# 1U_attenuvert.net
KiCad netlist of a schematic drawn in EAGLE
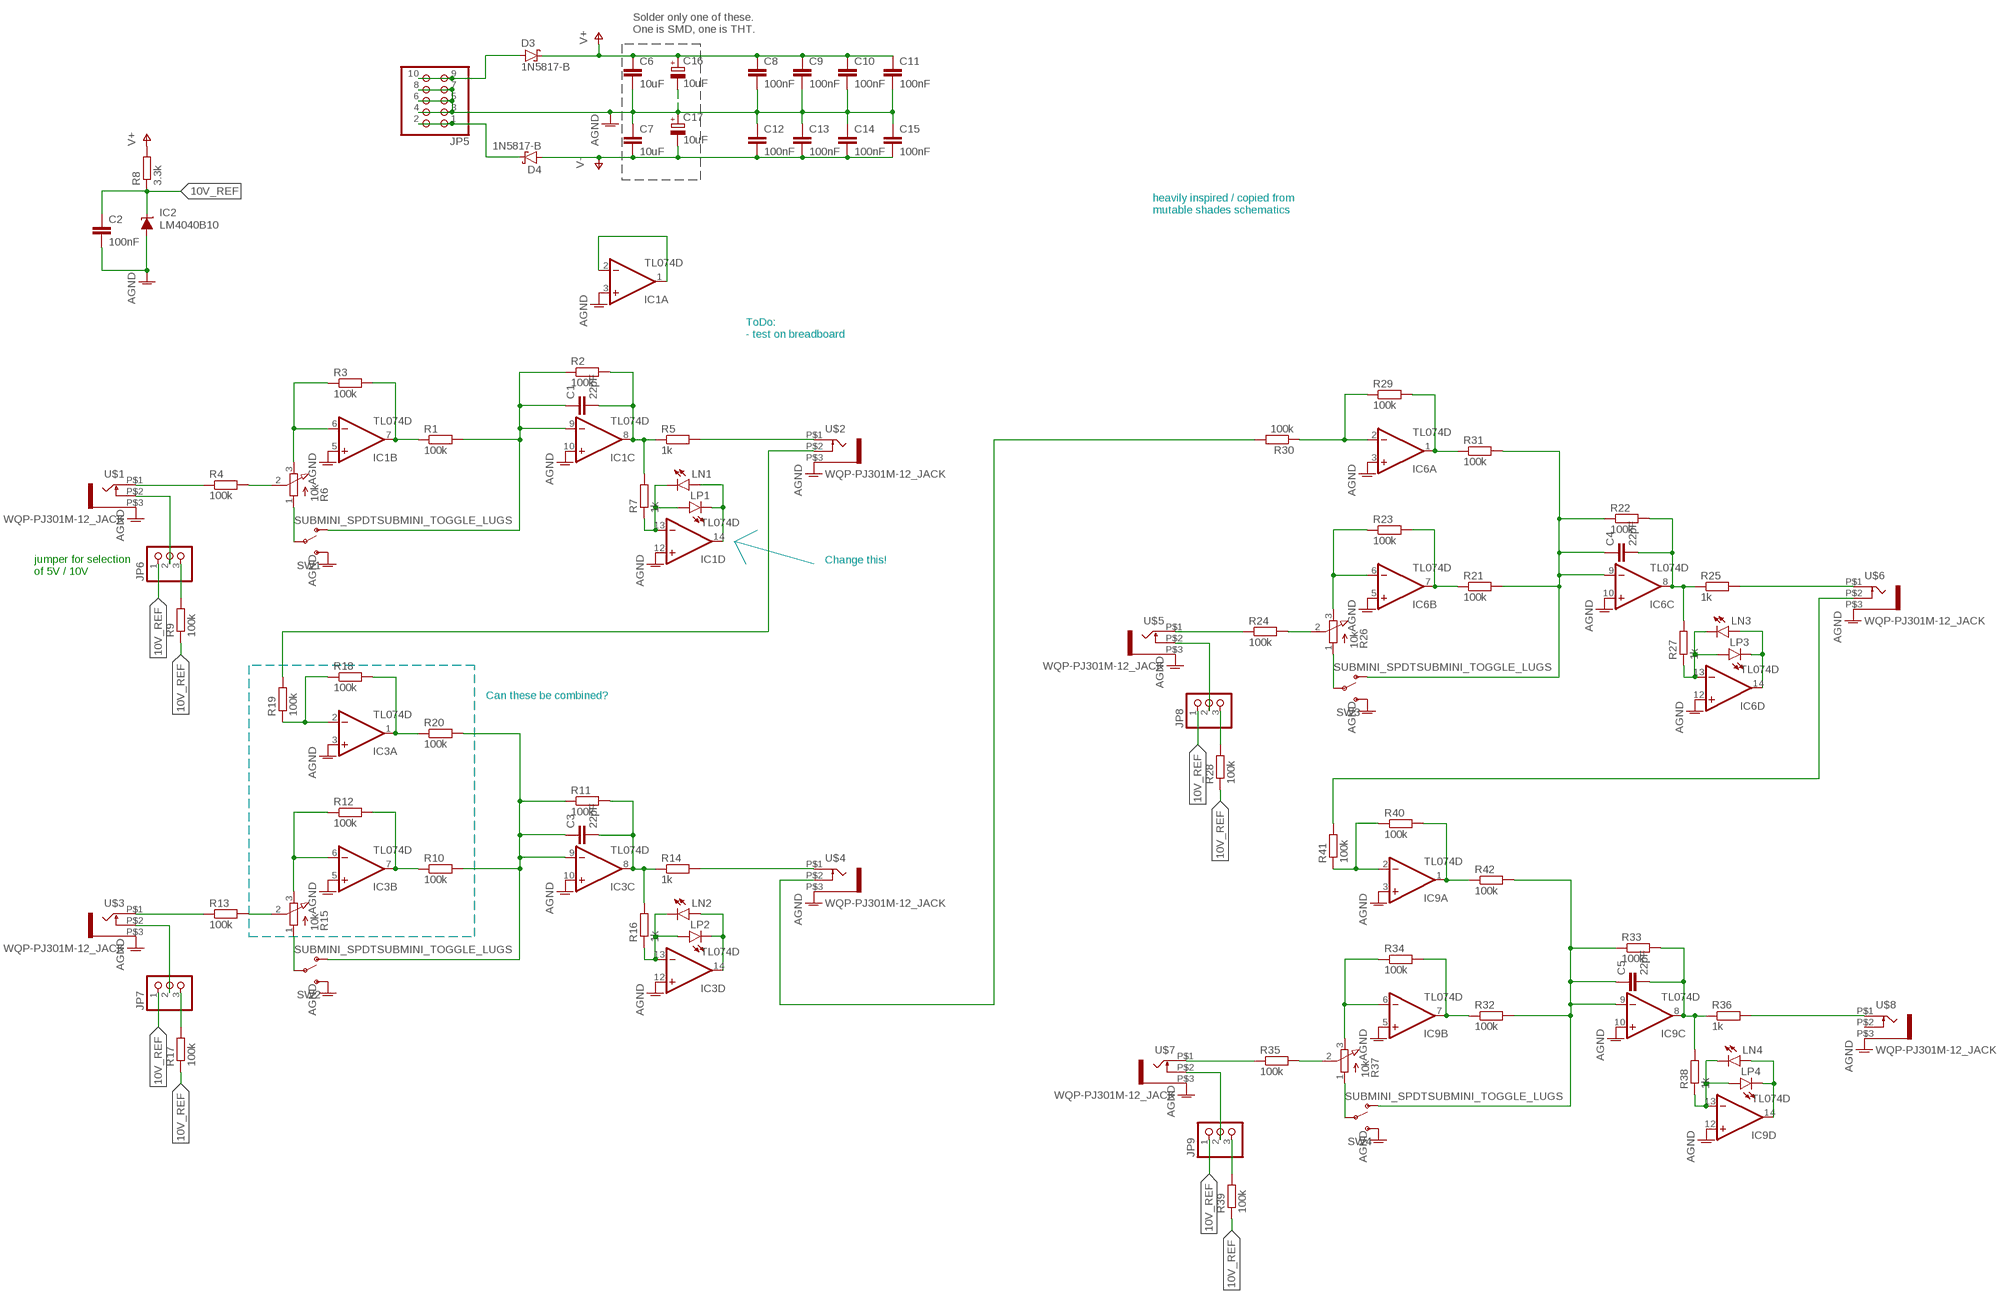
[diagram p0: schematic, sheet 1]

(export (version "E")
  (design (tool "Eeschema 10.0.6"))
  (components
    (comp (ref "C1")
      (value "22pF")
      (footprint "eagle-import:C0603")
      (libsource (lib "eagle-import") (part "C-EUC0603"))
    )
    (comp (ref "C2")
      (value "100nF")
      (footprint "eagle-import:C0603")
      (libsource (lib "eagle-import") (part "C-EUC0603"))
    )
    (comp (ref "C3")
      (value "22pF")
      (footprint "eagle-import:C0603")
      (libsource (lib "eagle-import") (part "C-EUC0603"))
    )
    (comp (ref "C4")
      (value "22pF")
      (footprint "eagle-import:C0603")
      (libsource (lib "eagle-import") (part "C-EUC0603"))
    )
    (comp (ref "C5")
      (value "22pF")
      (footprint "eagle-import:C0603")
      (libsource (lib "eagle-import") (part "C-EUC0603"))
    )
    (comp (ref "C6")
      (value "10uF")
      (footprint "eagle-import:C0805")
      (libsource (lib "eagle-import") (part "C-EUC0805"))
    )
    (comp (ref "C7")
      (value "10uF")
      (footprint "eagle-import:C0805")
      (libsource (lib "eagle-import") (part "C-EUC0805"))
    )
    (comp (ref "C8")
      (value "100nF")
      (footprint "eagle-import:C0603")
      (libsource (lib "eagle-import") (part "C-EUC0603"))
    )
    (comp (ref "C9")
      (value "100nF")
      (footprint "eagle-import:C0603")
      (libsource (lib "eagle-import") (part "C-EUC0603"))
    )
    (comp (ref "C10")
      (value "100nF")
      (footprint "eagle-import:C0603")
      (libsource (lib "eagle-import") (part "C-EUC0603"))
    )
    (comp (ref "C11")
      (value "100nF")
      (footprint "eagle-import:C0603")
      (libsource (lib "eagle-import") (part "C-EUC0603"))
    )
    (comp (ref "C12")
      (value "100nF")
      (footprint "eagle-import:C0603")
      (libsource (lib "eagle-import") (part "C-EUC0603"))
    )
    (comp (ref "C13")
      (value "100nF")
      (footprint "eagle-import:C0603")
      (libsource (lib "eagle-import") (part "C-EUC0603"))
    )
    (comp (ref "C14")
      (value "100nF")
      (footprint "eagle-import:C0603")
      (libsource (lib "eagle-import") (part "C-EUC0603"))
    )
    (comp (ref "C15")
      (value "100nF")
      (footprint "eagle-import:C0603")
      (libsource (lib "eagle-import") (part "C-EUC0603"))
    )
    (comp (ref "C16")
      (value "10uF")
      (footprint "eagle-import:E2,5-6")
      (libsource (lib "eagle-import") (part "CPOL-EUE2.5-6"))
    )
    (comp (ref "C17")
      (value "10uF")
      (footprint "eagle-import:E2,5-6")
      (libsource (lib "eagle-import") (part "CPOL-EUE2.5-6"))
    )
    (comp (ref "D3")
      (value "1N5817-B")
      (footprint "eagle-import:DO41-7.6")
      (libsource (lib "eagle-import") (part "1N5817-B"))
    )
    (comp (ref "D4")
      (value "1N5817-B")
      (footprint "eagle-import:DO41-7.6")
      (libsource (lib "eagle-import") (part "1N5817-B"))
    )
    (comp (ref "IC1")
      (value "TL074D")
      (footprint "eagle-import:SO14")
      (libsource (lib "eagle-import") (part "TL074D"))
    )
    (comp (ref "IC2")
      (value "LM4040B10")
      (footprint "eagle-import:DBZ_R-PDSO-G3")
      (fields (field (name "MPN") "LM4041A12IDBZR"))
      (libsource (lib "eagle-import") (part "LM4041DBZA12"))
    )
    (comp (ref "IC3")
      (value "TL074D")
      (footprint "eagle-import:SO14")
      (libsource (lib "eagle-import") (part "TL074D"))
    )
    (comp (ref "IC6")
      (value "TL074D")
      (footprint "eagle-import:SO14")
      (libsource (lib "eagle-import") (part "TL074D"))
    )
    (comp (ref "IC9")
      (value "TL074D")
      (footprint "eagle-import:SO14")
      (libsource (lib "eagle-import") (part "TL074D"))
    )
    (comp (ref "JP5")
      (value "PINHD-2X5")
      (footprint "eagle-import:2X05")
      (libsource (lib "eagle-import") (part "PINHD-2X5"))
    )
    (comp (ref "JP6")
      (value "PINHD-1X3")
      (footprint "eagle-import:1X03")
      (libsource (lib "eagle-import") (part "PINHD-1X3"))
    )
    (comp (ref "JP7")
      (value "PINHD-1X3")
      (footprint "eagle-import:1X03")
      (libsource (lib "eagle-import") (part "PINHD-1X3"))
    )
    (comp (ref "JP8")
      (value "PINHD-1X3")
      (footprint "eagle-import:1X03")
      (libsource (lib "eagle-import") (part "PINHD-1X3"))
    )
    (comp (ref "JP9")
      (value "PINHD-1X3")
      (footprint "eagle-import:1X03")
      (libsource (lib "eagle-import") (part "PINHD-1X3"))
    )
    (comp (ref "LN1")
      (value "LED3MM")
      (footprint "eagle-import:LED3MM")
      (libsource (lib "eagle-import") (part "LED3MM"))
    )
    (comp (ref "LN2")
      (value "LED3MM")
      (footprint "eagle-import:LED3MM")
      (libsource (lib "eagle-import") (part "LED3MM"))
    )
    (comp (ref "LN3")
      (value "LED3MM")
      (footprint "eagle-import:LED3MM")
      (libsource (lib "eagle-import") (part "LED3MM"))
    )
    (comp (ref "LN4")
      (value "LED3MM")
      (footprint "eagle-import:LED3MM")
      (libsource (lib "eagle-import") (part "LED3MM"))
    )
    (comp (ref "LP1")
      (value "LED3MM")
      (footprint "eagle-import:LED3MM")
      (libsource (lib "eagle-import") (part "LED3MM"))
    )
    (comp (ref "LP2")
      (value "LED3MM")
      (footprint "eagle-import:LED3MM")
      (libsource (lib "eagle-import") (part "LED3MM"))
    )
    (comp (ref "LP3")
      (value "LED3MM")
      (footprint "eagle-import:LED3MM")
      (libsource (lib "eagle-import") (part "LED3MM"))
    )
    (comp (ref "LP4")
      (value "LED3MM")
      (footprint "eagle-import:LED3MM")
      (libsource (lib "eagle-import") (part "LED3MM"))
    )
    (comp (ref "R1")
      (value "100k")
      (footprint "eagle-import:R0603")
      (libsource (lib "eagle-import") (part "R-EU_R0603"))
    )
    (comp (ref "R2")
      (value "100k")
      (footprint "eagle-import:R0603")
      (libsource (lib "eagle-import") (part "R-EU_R0603"))
    )
    (comp (ref "R3")
      (value "100k")
      (footprint "eagle-import:R0603")
      (libsource (lib "eagle-import") (part "R-EU_R0603"))
    )
    (comp (ref "R4")
      (value "100k")
      (footprint "eagle-import:R0603")
      (libsource (lib "eagle-import") (part "R-EU_R0603"))
    )
    (comp (ref "R5")
      (value "1k")
      (footprint "eagle-import:R0603")
      (libsource (lib "eagle-import") (part "R-EU_R0603"))
    )
    (comp (ref "R6")
      (value "10k")
      (footprint "eagle-import:EVUFXL")
      (libsource (lib "eagle-import") (part "EVULF2"))
    )
    (comp (ref "R7")
      (value "1k")
      (footprint "eagle-import:R0603")
      (libsource (lib "eagle-import") (part "R-EU_R0603"))
    )
    (comp (ref "R8")
      (value "3.3k")
      (footprint "eagle-import:R0603")
      (libsource (lib "eagle-import") (part "R-EU_R0603"))
    )
    (comp (ref "R9")
      (value "100k")
      (footprint "eagle-import:R0603")
      (libsource (lib "eagle-import") (part "R-EU_R0603"))
    )
    (comp (ref "R10")
      (value "100k")
      (footprint "eagle-import:R0603")
      (libsource (lib "eagle-import") (part "R-EU_R0603"))
    )
    (comp (ref "R11")
      (value "100k")
      (footprint "eagle-import:R0603")
      (libsource (lib "eagle-import") (part "R-EU_R0603"))
    )
    (comp (ref "R12")
      (value "100k")
      (footprint "eagle-import:R0603")
      (libsource (lib "eagle-import") (part "R-EU_R0603"))
    )
    (comp (ref "R13")
      (value "100k")
      (footprint "eagle-import:R0603")
      (libsource (lib "eagle-import") (part "R-EU_R0603"))
    )
    (comp (ref "R14")
      (value "1k")
      (footprint "eagle-import:R0603")
      (libsource (lib "eagle-import") (part "R-EU_R0603"))
    )
    (comp (ref "R15")
      (value "10k")
      (footprint "eagle-import:EVUFXL")
      (libsource (lib "eagle-import") (part "EVULF2"))
    )
    (comp (ref "R16")
      (value "1k")
      (footprint "eagle-import:R0603")
      (libsource (lib "eagle-import") (part "R-EU_R0603"))
    )
    (comp (ref "R17")
      (value "100k")
      (footprint "eagle-import:R0603")
      (libsource (lib "eagle-import") (part "R-EU_R0603"))
    )
    (comp (ref "R18")
      (value "100k")
      (footprint "eagle-import:R0603")
      (libsource (lib "eagle-import") (part "R-EU_R0603"))
    )
    (comp (ref "R19")
      (value "100k")
      (footprint "eagle-import:R0603")
      (libsource (lib "eagle-import") (part "R-EU_R0603"))
    )
    (comp (ref "R20")
      (value "100k")
      (footprint "eagle-import:R0603")
      (libsource (lib "eagle-import") (part "R-EU_R0603"))
    )
    (comp (ref "R21")
      (value "100k")
      (footprint "eagle-import:R0603")
      (libsource (lib "eagle-import") (part "R-EU_R0603"))
    )
    (comp (ref "R22")
      (value "100k")
      (footprint "eagle-import:R0603")
      (libsource (lib "eagle-import") (part "R-EU_R0603"))
    )
    (comp (ref "R23")
      (value "100k")
      (footprint "eagle-import:R0603")
      (libsource (lib "eagle-import") (part "R-EU_R0603"))
    )
    (comp (ref "R24")
      (value "100k")
      (footprint "eagle-import:R0603")
      (libsource (lib "eagle-import") (part "R-EU_R0603"))
    )
    (comp (ref "R25")
      (value "1k")
      (footprint "eagle-import:R0603")
      (libsource (lib "eagle-import") (part "R-EU_R0603"))
    )
    (comp (ref "R26")
      (value "10k")
      (footprint "eagle-import:EVUFXL")
      (libsource (lib "eagle-import") (part "EVULF2"))
    )
    (comp (ref "R27")
      (value "1k")
      (footprint "eagle-import:R0603")
      (libsource (lib "eagle-import") (part "R-EU_R0603"))
    )
    (comp (ref "R28")
      (value "100k")
      (footprint "eagle-import:R0603")
      (libsource (lib "eagle-import") (part "R-EU_R0603"))
    )
    (comp (ref "R29")
      (value "100k")
      (footprint "eagle-import:R0603")
      (libsource (lib "eagle-import") (part "R-EU_R0603"))
    )
    (comp (ref "R30")
      (value "100k")
      (footprint "eagle-import:R0603")
      (libsource (lib "eagle-import") (part "R-EU_R0603"))
    )
    (comp (ref "R31")
      (value "100k")
      (footprint "eagle-import:R0603")
      (libsource (lib "eagle-import") (part "R-EU_R0603"))
    )
    (comp (ref "R32")
      (value "100k")
      (footprint "eagle-import:R0603")
      (libsource (lib "eagle-import") (part "R-EU_R0603"))
    )
    (comp (ref "R33")
      (value "100k")
      (footprint "eagle-import:R0603")
      (libsource (lib "eagle-import") (part "R-EU_R0603"))
    )
    (comp (ref "R34")
      (value "100k")
      (footprint "eagle-import:R0603")
      (libsource (lib "eagle-import") (part "R-EU_R0603"))
    )
    (comp (ref "R35")
      (value "100k")
      (footprint "eagle-import:R0603")
      (libsource (lib "eagle-import") (part "R-EU_R0603"))
    )
    (comp (ref "R36")
      (value "1k")
      (footprint "eagle-import:R0603")
      (libsource (lib "eagle-import") (part "R-EU_R0603"))
    )
    (comp (ref "R37")
      (value "10k")
      (footprint "eagle-import:EVUFXL")
      (libsource (lib "eagle-import") (part "EVULF2"))
    )
    (comp (ref "R38")
      (value "1k")
      (footprint "eagle-import:R0603")
      (libsource (lib "eagle-import") (part "R-EU_R0603"))
    )
    (comp (ref "R39")
      (value "100k")
      (footprint "eagle-import:R0603")
      (libsource (lib "eagle-import") (part "R-EU_R0603"))
    )
    (comp (ref "R40")
      (value "100k")
      (footprint "eagle-import:R0603")
      (libsource (lib "eagle-import") (part "R-EU_R0603"))
    )
    (comp (ref "R41")
      (value "100k")
      (footprint "eagle-import:R0603")
      (libsource (lib "eagle-import") (part "R-EU_R0603"))
    )
    (comp (ref "R42")
      (value "100k")
      (footprint "eagle-import:R0603")
      (libsource (lib "eagle-import") (part "R-EU_R0603"))
    )
    (comp (ref "SW1")
      (value "SUBMINI_SPDTSUBMINI_TOGGLE_LUGS")
      (footprint "eagle-import:SUBMINI_TOGGLE_LUGS")
      (libsource (lib "eagle-import") (part "SUBMINI_SPDTSUBMINI_TOGGLE_LUGS"))
    )
    (comp (ref "SW2")
      (value "SUBMINI_SPDTSUBMINI_TOGGLE_LUGS")
      (footprint "eagle-import:SUBMINI_TOGGLE_LUGS")
      (libsource (lib "eagle-import") (part "SUBMINI_SPDTSUBMINI_TOGGLE_LUGS"))
    )
    (comp (ref "SW3")
      (value "SUBMINI_SPDTSUBMINI_TOGGLE_LUGS")
      (footprint "eagle-import:SUBMINI_TOGGLE_LUGS")
      (libsource (lib "eagle-import") (part "SUBMINI_SPDTSUBMINI_TOGGLE_LUGS"))
    )
    (comp (ref "SW4")
      (value "SUBMINI_SPDTSUBMINI_TOGGLE_LUGS")
      (footprint "eagle-import:SUBMINI_TOGGLE_LUGS")
      (libsource (lib "eagle-import") (part "SUBMINI_SPDTSUBMINI_TOGGLE_LUGS"))
    )
    (comp (ref "U$1")
      (value "WQP-PJ301M-12_JACK")
      (footprint "eagle-import:WQP-PJ301M-12_JACK")
      (libsource (lib "eagle-import") (part "WQP-PJ301M-12_JACK"))
    )
    (comp (ref "U$2")
      (value "WQP-PJ301M-12_JACK")
      (footprint "eagle-import:WQP-PJ301M-12_JACK")
      (libsource (lib "eagle-import") (part "WQP-PJ301M-12_JACK"))
    )
    (comp (ref "U$3")
      (value "WQP-PJ301M-12_JACK")
      (footprint "eagle-import:WQP-PJ301M-12_JACK")
      (libsource (lib "eagle-import") (part "WQP-PJ301M-12_JACK"))
    )
    (comp (ref "U$4")
      (value "WQP-PJ301M-12_JACK")
      (footprint "eagle-import:WQP-PJ301M-12_JACK")
      (libsource (lib "eagle-import") (part "WQP-PJ301M-12_JACK"))
    )
    (comp (ref "U$5")
      (value "WQP-PJ301M-12_JACK")
      (footprint "eagle-import:WQP-PJ301M-12_JACK")
      (libsource (lib "eagle-import") (part "WQP-PJ301M-12_JACK"))
    )
    (comp (ref "U$6")
      (value "WQP-PJ301M-12_JACK")
      (footprint "eagle-import:WQP-PJ301M-12_JACK")
      (libsource (lib "eagle-import") (part "WQP-PJ301M-12_JACK"))
    )
    (comp (ref "U$7")
      (value "WQP-PJ301M-12_JACK")
      (footprint "eagle-import:WQP-PJ301M-12_JACK")
      (libsource (lib "eagle-import") (part "WQP-PJ301M-12_JACK"))
    )
    (comp (ref "U$8")
      (value "WQP-PJ301M-12_JACK")
      (footprint "eagle-import:WQP-PJ301M-12_JACK")
      (libsource (lib "eagle-import") (part "WQP-PJ301M-12_JACK"))
    )
  )
  (nets
    (net (code "1") (name "10V_REF") (class "Default")
      (node (ref "C2") (pin "1") (pinfunction "1_1") (pintype "passive"))
      (node (ref "IC2") (pin "1") (pinfunction "C_1") (pintype "passive"))
      (node (ref "JP6") (pin "1") (pinfunction "1_1") (pintype "passive"))
      (node (ref "JP7") (pin "1") (pinfunction "1_1") (pintype "passive"))
      (node (ref "JP8") (pin "1") (pinfunction "1_1") (pintype "passive"))
      (node (ref "JP9") (pin "1") (pinfunction "1_1") (pintype "passive"))
      (node (ref "R17") (pin "1") (pinfunction "1_1") (pintype "passive"))
      (node (ref "R28") (pin "1") (pinfunction "1_1") (pintype "passive"))
      (node (ref "R39") (pin "1") (pinfunction "1_1") (pintype "passive"))
      (node (ref "R8") (pin "1") (pinfunction "1_1") (pintype "passive"))
      (node (ref "R9") (pin "1") (pinfunction "1_1") (pintype "passive"))
    )
    (net (code "2") (name "AGND") (class "Default")
      (node (ref "C10") (pin "2") (pinfunction "2_2") (pintype "passive"))
      (node (ref "C11") (pin "2") (pinfunction "2_2") (pintype "passive"))
      (node (ref "C12") (pin "1") (pinfunction "1_1") (pintype "passive"))
      (node (ref "C13") (pin "1") (pinfunction "1_1") (pintype "passive"))
      (node (ref "C14") (pin "1") (pinfunction "1_1") (pintype "passive"))
      (node (ref "C15") (pin "1") (pinfunction "1_1") (pintype "passive"))
      (node (ref "C16") (pin "-") (pinfunction "-_-") (pintype "passive"))
      (node (ref "C17") (pin "+") (pinfunction "+_+") (pintype "passive"))
      (node (ref "C2") (pin "2") (pinfunction "2_2") (pintype "passive"))
      (node (ref "C6") (pin "2") (pinfunction "2_2") (pintype "passive"))
      (node (ref "C7") (pin "1") (pinfunction "1_1") (pintype "passive"))
      (node (ref "C8") (pin "2") (pinfunction "2_2") (pintype "passive"))
      (node (ref "C9") (pin "2") (pinfunction "2_2") (pintype "passive"))
      (node (ref "IC1") (pin "10") (pinfunction "+IN_10") (pintype "input"))
      (node (ref "IC1") (pin "12") (pinfunction "+IN_12") (pintype "input"))
      (node (ref "IC1") (pin "3") (pinfunction "+IN_3") (pintype "input"))
      (node (ref "IC1") (pin "5") (pinfunction "+IN_5") (pintype "input"))
      (node (ref "IC2") (pin "2") (pinfunction "A_2") (pintype "passive"))
      (node (ref "IC3") (pin "10") (pinfunction "+IN_10") (pintype "input"))
      (node (ref "IC3") (pin "12") (pinfunction "+IN_12") (pintype "input"))
      (node (ref "IC3") (pin "3") (pinfunction "+IN_3") (pintype "input"))
      (node (ref "IC3") (pin "5") (pinfunction "+IN_5") (pintype "input"))
      (node (ref "IC6") (pin "10") (pinfunction "+IN_10") (pintype "input"))
      (node (ref "IC6") (pin "12") (pinfunction "+IN_12") (pintype "input"))
      (node (ref "IC6") (pin "3") (pinfunction "+IN_3") (pintype "input"))
      (node (ref "IC6") (pin "5") (pinfunction "+IN_5") (pintype "input"))
      (node (ref "IC9") (pin "10") (pinfunction "+IN_10") (pintype "input"))
      (node (ref "IC9") (pin "12") (pinfunction "+IN_12") (pintype "input"))
      (node (ref "IC9") (pin "3") (pinfunction "+IN_3") (pintype "input"))
      (node (ref "IC9") (pin "5") (pinfunction "+IN_5") (pintype "input"))
      (node (ref "JP5") (pin "3") (pinfunction "3_3") (pintype "passive"))
      (node (ref "JP5") (pin "4") (pinfunction "4_4") (pintype "passive"))
      (node (ref "JP5") (pin "5") (pinfunction "5_5") (pintype "passive"))
      (node (ref "JP5") (pin "6") (pinfunction "6_6") (pintype "passive"))
      (node (ref "JP5") (pin "7") (pinfunction "7_7") (pintype "passive"))
      (node (ref "JP5") (pin "8") (pinfunction "8_8") (pintype "passive"))
      (node (ref "SW1") (pin "3") (pinfunction "S_3") (pintype "passive"))
      (node (ref "SW2") (pin "3") (pinfunction "S_3") (pintype "passive"))
      (node (ref "SW3") (pin "3") (pinfunction "S_3") (pintype "passive"))
      (node (ref "SW4") (pin "3") (pinfunction "S_3") (pintype "passive"))
      (node (ref "U$1") (pin "P$3") (pinfunction "1_P$3") (pintype "passive"))
      (node (ref "U$2") (pin "P$3") (pinfunction "1_P$3") (pintype "passive"))
      (node (ref "U$3") (pin "P$3") (pinfunction "1_P$3") (pintype "passive"))
      (node (ref "U$4") (pin "P$3") (pinfunction "1_P$3") (pintype "passive"))
      (node (ref "U$5") (pin "P$3") (pinfunction "1_P$3") (pintype "passive"))
      (node (ref "U$6") (pin "P$3") (pinfunction "1_P$3") (pintype "passive"))
      (node (ref "U$7") (pin "P$3") (pinfunction "1_P$3") (pintype "passive"))
      (node (ref "U$8") (pin "P$3") (pinfunction "1_P$3") (pintype "passive"))
    )
    (net (code "3") (name "Net-(D3-PadA)") (class "Default")
      (node (ref "D3") (pin "A") (pinfunction "A_A") (pintype "passive"))
      (node (ref "JP5") (pin "10") (pinfunction "10_10") (pintype "passive"))
      (node (ref "JP5") (pin "9") (pinfunction "9_9") (pintype "passive"))
    )
    (net (code "4") (name "Net-(D4-PadC)") (class "Default")
      (node (ref "D4") (pin "C") (pinfunction "C_C") (pintype "passive"))
      (node (ref "JP5") (pin "1") (pinfunction "1_1") (pintype "passive"))
      (node (ref "JP5") (pin "2") (pinfunction "2_2") (pintype "passive"))
    )
    (net (code "5") (name "Net-(IC1A--IN)") (class "Default")
      (node (ref "IC1") (pin "1") (pinfunction "OUT_1") (pintype "output"))
      (node (ref "IC1") (pin "2") (pinfunction "-IN_2") (pintype "input"))
    )
    (net (code "6") (name "Net-(IC1B--IN)") (class "Default")
      (node (ref "IC1") (pin "6") (pinfunction "-IN_6") (pintype "input"))
      (node (ref "R3") (pin "1") (pinfunction "1_1") (pintype "passive"))
      (node (ref "R6") (pin "3") (pinfunction "E_3") (pintype "passive"))
    )
    (net (code "7") (name "Net-(IC1B-OUT)") (class "Default")
      (node (ref "IC1") (pin "7") (pinfunction "OUT_7") (pintype "output"))
      (node (ref "R1") (pin "1") (pinfunction "1_1") (pintype "passive"))
      (node (ref "R3") (pin "2") (pinfunction "2_2") (pintype "passive"))
    )
    (net (code "8") (name "Net-(IC1C--IN)") (class "Default")
      (node (ref "C1") (pin "1") (pinfunction "1_1") (pintype "passive"))
      (node (ref "IC1") (pin "9") (pinfunction "-IN_9") (pintype "input"))
      (node (ref "R1") (pin "2") (pinfunction "2_2") (pintype "passive"))
      (node (ref "R2") (pin "1") (pinfunction "1_1") (pintype "passive"))
      (node (ref "SW1") (pin "1") (pinfunction "O_1") (pintype "passive"))
    )
    (net (code "9") (name "Net-(IC1C-OUT)") (class "Default")
      (node (ref "C1") (pin "2") (pinfunction "2_2") (pintype "passive"))
      (node (ref "IC1") (pin "8") (pinfunction "OUT_8") (pintype "output"))
      (node (ref "R2") (pin "2") (pinfunction "2_2") (pintype "passive"))
      (node (ref "R5") (pin "1") (pinfunction "1_1") (pintype "passive"))
      (node (ref "R7") (pin "2") (pinfunction "2_2") (pintype "passive"))
    )
    (net (code "10") (name "Net-(IC1D--IN)") (class "Default")
      (node (ref "IC1") (pin "13") (pinfunction "-IN_13") (pintype "input"))
      (node (ref "LN1") (pin "K") (pinfunction "C_K") (pintype "passive"))
      (node (ref "LP1") (pin "A") (pinfunction "A_A") (pintype "passive"))
      (node (ref "R7") (pin "1") (pinfunction "1_1") (pintype "passive"))
    )
    (net (code "11") (name "Net-(IC1D-OUT)") (class "Default")
      (node (ref "IC1") (pin "14") (pinfunction "OUT_14") (pintype "output"))
      (node (ref "LN1") (pin "A") (pinfunction "A_A") (pintype "passive"))
      (node (ref "LP1") (pin "K") (pinfunction "C_K") (pintype "passive"))
    )
    (net (code "12") (name "Net-(IC3A--IN)") (class "Default")
      (node (ref "IC3") (pin "2") (pinfunction "-IN_2") (pintype "input"))
      (node (ref "R18") (pin "1") (pinfunction "1_1") (pintype "passive"))
      (node (ref "R19") (pin "1") (pinfunction "1_1") (pintype "passive"))
    )
    (net (code "13") (name "Net-(IC3A-OUT)") (class "Default")
      (node (ref "IC3") (pin "1") (pinfunction "OUT_1") (pintype "output"))
      (node (ref "R18") (pin "2") (pinfunction "2_2") (pintype "passive"))
      (node (ref "R20") (pin "1") (pinfunction "1_1") (pintype "passive"))
    )
    (net (code "14") (name "Net-(IC3B--IN)") (class "Default")
      (node (ref "IC3") (pin "6") (pinfunction "-IN_6") (pintype "input"))
      (node (ref "R12") (pin "1") (pinfunction "1_1") (pintype "passive"))
      (node (ref "R15") (pin "3") (pinfunction "E_3") (pintype "passive"))
    )
    (net (code "15") (name "Net-(IC3B-OUT)") (class "Default")
      (node (ref "IC3") (pin "7") (pinfunction "OUT_7") (pintype "output"))
      (node (ref "R10") (pin "1") (pinfunction "1_1") (pintype "passive"))
      (node (ref "R12") (pin "2") (pinfunction "2_2") (pintype "passive"))
    )
    (net (code "16") (name "Net-(IC3C--IN)") (class "Default")
      (node (ref "C3") (pin "1") (pinfunction "1_1") (pintype "passive"))
      (node (ref "IC3") (pin "9") (pinfunction "-IN_9") (pintype "input"))
      (node (ref "R10") (pin "2") (pinfunction "2_2") (pintype "passive"))
      (node (ref "R11") (pin "1") (pinfunction "1_1") (pintype "passive"))
      (node (ref "R20") (pin "2") (pinfunction "2_2") (pintype "passive"))
      (node (ref "SW2") (pin "1") (pinfunction "O_1") (pintype "passive"))
    )
    (net (code "17") (name "Net-(IC3C-OUT)") (class "Default")
      (node (ref "C3") (pin "2") (pinfunction "2_2") (pintype "passive"))
      (node (ref "IC3") (pin "8") (pinfunction "OUT_8") (pintype "output"))
      (node (ref "R11") (pin "2") (pinfunction "2_2") (pintype "passive"))
      (node (ref "R14") (pin "1") (pinfunction "1_1") (pintype "passive"))
      (node (ref "R16") (pin "2") (pinfunction "2_2") (pintype "passive"))
    )
    (net (code "18") (name "Net-(IC3D--IN)") (class "Default")
      (node (ref "IC3") (pin "13") (pinfunction "-IN_13") (pintype "input"))
      (node (ref "LN2") (pin "K") (pinfunction "C_K") (pintype "passive"))
      (node (ref "LP2") (pin "A") (pinfunction "A_A") (pintype "passive"))
      (node (ref "R16") (pin "1") (pinfunction "1_1") (pintype "passive"))
    )
    (net (code "19") (name "Net-(IC3D-OUT)") (class "Default")
      (node (ref "IC3") (pin "14") (pinfunction "OUT_14") (pintype "output"))
      (node (ref "LN2") (pin "A") (pinfunction "A_A") (pintype "passive"))
      (node (ref "LP2") (pin "K") (pinfunction "C_K") (pintype "passive"))
    )
    (net (code "20") (name "Net-(IC6A--IN)") (class "Default")
      (node (ref "IC6") (pin "2") (pinfunction "-IN_2") (pintype "input"))
      (node (ref "R29") (pin "1") (pinfunction "1_1") (pintype "passive"))
      (node (ref "R30") (pin "1") (pinfunction "1_1") (pintype "passive"))
    )
    (net (code "21") (name "Net-(IC6A-OUT)") (class "Default")
      (node (ref "IC6") (pin "1") (pinfunction "OUT_1") (pintype "output"))
      (node (ref "R29") (pin "2") (pinfunction "2_2") (pintype "passive"))
      (node (ref "R31") (pin "1") (pinfunction "1_1") (pintype "passive"))
    )
    (net (code "22") (name "Net-(IC6B--IN)") (class "Default")
      (node (ref "IC6") (pin "6") (pinfunction "-IN_6") (pintype "input"))
      (node (ref "R23") (pin "1") (pinfunction "1_1") (pintype "passive"))
      (node (ref "R26") (pin "3") (pinfunction "E_3") (pintype "passive"))
    )
    (net (code "23") (name "Net-(IC6B-OUT)") (class "Default")
      (node (ref "IC6") (pin "7") (pinfunction "OUT_7") (pintype "output"))
      (node (ref "R21") (pin "1") (pinfunction "1_1") (pintype "passive"))
      (node (ref "R23") (pin "2") (pinfunction "2_2") (pintype "passive"))
    )
    (net (code "24") (name "Net-(IC6C--IN)") (class "Default")
      (node (ref "C4") (pin "1") (pinfunction "1_1") (pintype "passive"))
      (node (ref "IC6") (pin "9") (pinfunction "-IN_9") (pintype "input"))
      (node (ref "R21") (pin "2") (pinfunction "2_2") (pintype "passive"))
      (node (ref "R22") (pin "1") (pinfunction "1_1") (pintype "passive"))
      (node (ref "R31") (pin "2") (pinfunction "2_2") (pintype "passive"))
      (node (ref "SW3") (pin "1") (pinfunction "O_1") (pintype "passive"))
    )
    (net (code "25") (name "Net-(IC6C-OUT)") (class "Default")
      (node (ref "C4") (pin "2") (pinfunction "2_2") (pintype "passive"))
      (node (ref "IC6") (pin "8") (pinfunction "OUT_8") (pintype "output"))
      (node (ref "R22") (pin "2") (pinfunction "2_2") (pintype "passive"))
      (node (ref "R25") (pin "1") (pinfunction "1_1") (pintype "passive"))
      (node (ref "R27") (pin "2") (pinfunction "2_2") (pintype "passive"))
    )
    (net (code "26") (name "Net-(IC6D--IN)") (class "Default")
      (node (ref "IC6") (pin "13") (pinfunction "-IN_13") (pintype "input"))
      (node (ref "LN3") (pin "K") (pinfunction "C_K") (pintype "passive"))
      (node (ref "LP3") (pin "A") (pinfunction "A_A") (pintype "passive"))
      (node (ref "R27") (pin "1") (pinfunction "1_1") (pintype "passive"))
    )
    (net (code "27") (name "Net-(IC6D-OUT)") (class "Default")
      (node (ref "IC6") (pin "14") (pinfunction "OUT_14") (pintype "output"))
      (node (ref "LN3") (pin "A") (pinfunction "A_A") (pintype "passive"))
      (node (ref "LP3") (pin "K") (pinfunction "C_K") (pintype "passive"))
    )
    (net (code "28") (name "Net-(IC9A--IN)") (class "Default")
      (node (ref "IC9") (pin "2") (pinfunction "-IN_2") (pintype "input"))
      (node (ref "R40") (pin "1") (pinfunction "1_1") (pintype "passive"))
      (node (ref "R41") (pin "1") (pinfunction "1_1") (pintype "passive"))
    )
    (net (code "29") (name "Net-(IC9A-OUT)") (class "Default")
      (node (ref "IC9") (pin "1") (pinfunction "OUT_1") (pintype "output"))
      (node (ref "R40") (pin "2") (pinfunction "2_2") (pintype "passive"))
      (node (ref "R42") (pin "1") (pinfunction "1_1") (pintype "passive"))
    )
    (net (code "30") (name "Net-(IC9B--IN)") (class "Default")
      (node (ref "IC9") (pin "6") (pinfunction "-IN_6") (pintype "input"))
      (node (ref "R34") (pin "1") (pinfunction "1_1") (pintype "passive"))
      (node (ref "R37") (pin "3") (pinfunction "E_3") (pintype "passive"))
    )
    (net (code "31") (name "Net-(IC9B-OUT)") (class "Default")
      (node (ref "IC9") (pin "7") (pinfunction "OUT_7") (pintype "output"))
      (node (ref "R32") (pin "1") (pinfunction "1_1") (pintype "passive"))
      (node (ref "R34") (pin "2") (pinfunction "2_2") (pintype "passive"))
    )
    (net (code "32") (name "Net-(IC9C--IN)") (class "Default")
      (node (ref "C5") (pin "1") (pinfunction "1_1") (pintype "passive"))
      (node (ref "IC9") (pin "9") (pinfunction "-IN_9") (pintype "input"))
      (node (ref "R32") (pin "2") (pinfunction "2_2") (pintype "passive"))
      (node (ref "R33") (pin "1") (pinfunction "1_1") (pintype "passive"))
      (node (ref "R42") (pin "2") (pinfunction "2_2") (pintype "passive"))
      (node (ref "SW4") (pin "1") (pinfunction "O_1") (pintype "passive"))
    )
    (net (code "33") (name "Net-(IC9C-OUT)") (class "Default")
      (node (ref "C5") (pin "2") (pinfunction "2_2") (pintype "passive"))
      (node (ref "IC9") (pin "8") (pinfunction "OUT_8") (pintype "output"))
      (node (ref "R33") (pin "2") (pinfunction "2_2") (pintype "passive"))
      (node (ref "R36") (pin "1") (pinfunction "1_1") (pintype "passive"))
      (node (ref "R38") (pin "2") (pinfunction "2_2") (pintype "passive"))
    )
    (net (code "34") (name "Net-(IC9D--IN)") (class "Default")
      (node (ref "IC9") (pin "13") (pinfunction "-IN_13") (pintype "input"))
      (node (ref "LN4") (pin "K") (pinfunction "C_K") (pintype "passive"))
      (node (ref "LP4") (pin "A") (pinfunction "A_A") (pintype "passive"))
      (node (ref "R38") (pin "1") (pinfunction "1_1") (pintype "passive"))
    )
    (net (code "35") (name "Net-(IC9D-OUT)") (class "Default")
      (node (ref "IC9") (pin "14") (pinfunction "OUT_14") (pintype "output"))
      (node (ref "LN4") (pin "A") (pinfunction "A_A") (pintype "passive"))
      (node (ref "LP4") (pin "K") (pinfunction "C_K") (pintype "passive"))
    )
    (net (code "36") (name "Net-(JP6-Pad3)") (class "Default")
      (node (ref "JP6") (pin "3") (pinfunction "3_3") (pintype "passive"))
      (node (ref "R9") (pin "2") (pinfunction "2_2") (pintype "passive"))
    )
    (net (code "37") (name "Net-(JP7-Pad3)") (class "Default")
      (node (ref "JP7") (pin "3") (pinfunction "3_3") (pintype "passive"))
      (node (ref "R17") (pin "2") (pinfunction "2_2") (pintype "passive"))
    )
    (net (code "38") (name "Net-(JP8-Pad3)") (class "Default")
      (node (ref "JP8") (pin "3") (pinfunction "3_3") (pintype "passive"))
      (node (ref "R28") (pin "2") (pinfunction "2_2") (pintype "passive"))
    )
    (net (code "39") (name "Net-(JP9-Pad3)") (class "Default")
      (node (ref "JP9") (pin "3") (pinfunction "3_3") (pintype "passive"))
      (node (ref "R39") (pin "2") (pinfunction "2_2") (pintype "passive"))
    )
    (net (code "40") (name "Net-(R6-A)") (class "Default")
      (node (ref "R6") (pin "1") (pinfunction "A_1") (pintype "passive"))
      (node (ref "SW1") (pin "COM") (pinfunction "COMMON_COM") (pintype "passive"))
    )
    (net (code "41") (name "Net-(R6-S)") (class "Default")
      (node (ref "R4") (pin "2") (pinfunction "2_2") (pintype "passive"))
      (node (ref "R6") (pin "2") (pinfunction "S_2") (pintype "passive"))
    )
    (net (code "42") (name "Net-(R15-A)") (class "Default")
      (node (ref "R15") (pin "1") (pinfunction "A_1") (pintype "passive"))
      (node (ref "SW2") (pin "COM") (pinfunction "COMMON_COM") (pintype "passive"))
    )
    (net (code "43") (name "Net-(R15-S)") (class "Default")
      (node (ref "R13") (pin "2") (pinfunction "2_2") (pintype "passive"))
      (node (ref "R15") (pin "2") (pinfunction "S_2") (pintype "passive"))
    )
    (net (code "44") (name "Net-(R26-A)") (class "Default")
      (node (ref "R26") (pin "1") (pinfunction "A_1") (pintype "passive"))
      (node (ref "SW3") (pin "COM") (pinfunction "COMMON_COM") (pintype "passive"))
    )
    (net (code "45") (name "Net-(R26-S)") (class "Default")
      (node (ref "R24") (pin "2") (pinfunction "2_2") (pintype "passive"))
      (node (ref "R26") (pin "2") (pinfunction "S_2") (pintype "passive"))
    )
    (net (code "46") (name "Net-(R37-A)") (class "Default")
      (node (ref "R37") (pin "1") (pinfunction "A_1") (pintype "passive"))
      (node (ref "SW4") (pin "COM") (pinfunction "COMMON_COM") (pintype "passive"))
    )
    (net (code "47") (name "Net-(R37-S)") (class "Default")
      (node (ref "R35") (pin "2") (pinfunction "2_2") (pintype "passive"))
      (node (ref "R37") (pin "2") (pinfunction "S_2") (pintype "passive"))
    )
    (net (code "48") (name "Net-(U$1-2)") (class "Default")
      (node (ref "R4") (pin "1") (pinfunction "1_1") (pintype "passive"))
      (node (ref "U$1") (pin "P$1") (pinfunction "2_P$1") (pintype "passive"))
    )
    (net (code "49") (name "Net-(U$1-3)") (class "Default")
      (node (ref "JP6") (pin "2") (pinfunction "2_2") (pintype "passive"))
      (node (ref "U$1") (pin "P$2") (pinfunction "3_P$2") (pintype "passive"))
    )
    (net (code "50") (name "Net-(U$2-2)") (class "Default")
      (node (ref "R5") (pin "2") (pinfunction "2_2") (pintype "passive"))
      (node (ref "U$2") (pin "P$1") (pinfunction "2_P$1") (pintype "passive"))
    )
    (net (code "51") (name "Net-(U$2-3)") (class "Default")
      (node (ref "R19") (pin "2") (pinfunction "2_2") (pintype "passive"))
      (node (ref "U$2") (pin "P$2") (pinfunction "3_P$2") (pintype "passive"))
    )
    (net (code "52") (name "Net-(U$3-2)") (class "Default")
      (node (ref "R13") (pin "1") (pinfunction "1_1") (pintype "passive"))
      (node (ref "U$3") (pin "P$1") (pinfunction "2_P$1") (pintype "passive"))
    )
    (net (code "53") (name "Net-(U$3-3)") (class "Default")
      (node (ref "JP7") (pin "2") (pinfunction "2_2") (pintype "passive"))
      (node (ref "U$3") (pin "P$2") (pinfunction "3_P$2") (pintype "passive"))
    )
    (net (code "54") (name "Net-(U$4-2)") (class "Default")
      (node (ref "R14") (pin "2") (pinfunction "2_2") (pintype "passive"))
      (node (ref "U$4") (pin "P$1") (pinfunction "2_P$1") (pintype "passive"))
    )
    (net (code "55") (name "Net-(U$4-3)") (class "Default")
      (node (ref "R30") (pin "2") (pinfunction "2_2") (pintype "passive"))
      (node (ref "U$4") (pin "P$2") (pinfunction "3_P$2") (pintype "passive"))
    )
    (net (code "56") (name "Net-(U$5-2)") (class "Default")
      (node (ref "R24") (pin "1") (pinfunction "1_1") (pintype "passive"))
      (node (ref "U$5") (pin "P$1") (pinfunction "2_P$1") (pintype "passive"))
    )
    (net (code "57") (name "Net-(U$5-3)") (class "Default")
      (node (ref "JP8") (pin "2") (pinfunction "2_2") (pintype "passive"))
      (node (ref "U$5") (pin "P$2") (pinfunction "3_P$2") (pintype "passive"))
    )
    (net (code "58") (name "Net-(U$6-2)") (class "Default")
      (node (ref "R25") (pin "2") (pinfunction "2_2") (pintype "passive"))
      (node (ref "U$6") (pin "P$1") (pinfunction "2_P$1") (pintype "passive"))
    )
    (net (code "59") (name "Net-(U$6-3)") (class "Default")
      (node (ref "R41") (pin "2") (pinfunction "2_2") (pintype "passive"))
      (node (ref "U$6") (pin "P$2") (pinfunction "3_P$2") (pintype "passive"))
    )
    (net (code "60") (name "Net-(U$7-2)") (class "Default")
      (node (ref "R35") (pin "1") (pinfunction "1_1") (pintype "passive"))
      (node (ref "U$7") (pin "P$1") (pinfunction "2_P$1") (pintype "passive"))
    )
    (net (code "61") (name "Net-(U$7-3)") (class "Default")
      (node (ref "JP9") (pin "2") (pinfunction "2_2") (pintype "passive"))
      (node (ref "U$7") (pin "P$2") (pinfunction "3_P$2") (pintype "passive"))
    )
    (net (code "62") (name "Net-(U$8-2)") (class "Default")
      (node (ref "R36") (pin "2") (pinfunction "2_2") (pintype "passive"))
      (node (ref "U$8") (pin "P$1") (pinfunction "2_P$1") (pintype "passive"))
    )
    (net (code "63") (name "V+") (class "Default")
      (node (ref "C10") (pin "1") (pinfunction "1_1") (pintype "passive"))
      (node (ref "C11") (pin "1") (pinfunction "1_1") (pintype "passive"))
      (node (ref "C16") (pin "+") (pinfunction "+_+") (pintype "passive"))
      (node (ref "C6") (pin "1") (pinfunction "1_1") (pintype "passive"))
      (node (ref "C8") (pin "1") (pinfunction "1_1") (pintype "passive"))
      (node (ref "C9") (pin "1") (pinfunction "1_1") (pintype "passive"))
      (node (ref "D3") (pin "C") (pinfunction "C_C") (pintype "passive"))
      (node (ref "R8") (pin "2") (pinfunction "2_2") (pintype "passive"))
    )
    (net (code "64") (name "V-") (class "Default")
      (node (ref "C12") (pin "2") (pinfunction "2_2") (pintype "passive"))
      (node (ref "C13") (pin "2") (pinfunction "2_2") (pintype "passive"))
      (node (ref "C14") (pin "2") (pinfunction "2_2") (pintype "passive"))
      (node (ref "C15") (pin "2") (pinfunction "2_2") (pintype "passive"))
      (node (ref "C17") (pin "-") (pinfunction "-_-") (pintype "passive"))
      (node (ref "C7") (pin "2") (pinfunction "2_2") (pintype "passive"))
      (node (ref "D4") (pin "A") (pinfunction "A_A") (pintype "passive"))
    )
    (net (code "65") (name "unconnected-(U$8-3-PadP$2)") (class "Default")
      (node (ref "U$8") (pin "P$2") (pinfunction "3_P$2") (pintype "passive"))
    )
  )
)
